# 02.net
KiCad netlist of a schematic drawn in Altium Designer
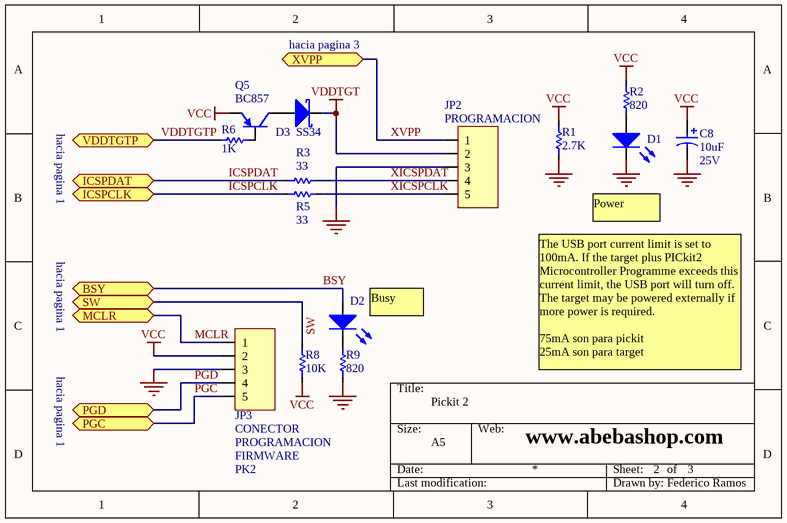
[diagram p0: 02.SchDoc]

(export (version "E")
  (design (tool "Eeschema 10.0.6"))
  (components
    (comp (ref "C8")
      (value "10uF")
      (footprint "1206P")
      (description "Capacitor Polarizado")
      (fields (field (name "VOLTAJE") "25V") (field (name "Comment") "Cap Pol"))
      (libsource (lib "FEDE") (part "Cap Pol"))
    )
    (comp (ref "D1")
      (value "LED")
      (footprint "1206P")
      (description "Led")
      (libsource (lib "FEDE") (part "LED"))
    )
    (comp (ref "D2")
      (value "LED")
      (footprint "1206P")
      (description "Led")
      (libsource (lib "FEDE") (part "LED"))
    )
    (comp (ref "D3")
      (value "SS34")
      (footprint "D64")
      (description "Schottky Diode 3A 40V")
      (libsource (lib "FEDE") (part "1N5822"))
    )
    (comp (ref "JP2")
      (value "Header5x1")
      (footprint "HDR5x1")
      (description "Header 5x1")
      (fields (field (name "PRICE") "PROGRAMACION"))
      (libsource (lib "FEDE") (part "Header5x1"))
    )
    (comp (ref "JP3")
      (value "Header5x1")
      (footprint "HDR5x1")
      (description "Header 5x1")
      (fields
        (field (name "PRICE") "CONECTOR")
        (field (name "ALTIUM_UNNAMED_1") "PROGRAMACION")
        (field (name "ALTIUM_UNNAMED_2") "FIRMWARE")
        (field (name "ALTIUM_UNNAMED_3") "PK2")
      )
      (libsource (lib "FEDE") (part "Header5x1"))
    )
    (comp (ref "Q5")
      (value "BC857")
      (footprint "SOT23")
      (description "100mA 65V PNP Bipolar Transistor")
      (libsource (lib "FEDE") (part "BC856A"))
    )
    (comp (ref "R1")
      (value "2.7K")
      (footprint "1206NP")
      (description "Resistor")
      (fields (field (name "POWER") "0.25W") (field (name "Comment") "Res"))
      (libsource (lib "FEDE") (part "Res"))
    )
    (comp (ref "R2")
      (value "820")
      (footprint "1206NP")
      (description "Resistor")
      (fields (field (name "POWER") "0.25W") (field (name "Comment") "Res"))
      (libsource (lib "FEDE") (part "Res"))
    )
    (comp (ref "R3")
      (value "33")
      (footprint "1206NP")
      (description "Resistor")
      (fields (field (name "POWER") "0.25W") (field (name "Comment") "Res"))
      (libsource (lib "FEDE") (part "Res"))
    )
    (comp (ref "R5")
      (value "33")
      (footprint "1206NP")
      (description "Resistor")
      (fields (field (name "POWER") "0.25W") (field (name "Comment") "Res"))
      (libsource (lib "FEDE") (part "Res"))
    )
    (comp (ref "R6")
      (value "1K")
      (footprint "1206NP")
      (description "Resistor")
      (fields (field (name "POWER") "0.25W") (field (name "Comment") "Res"))
      (libsource (lib "FEDE") (part "Res"))
    )
    (comp (ref "R8")
      (value "10K")
      (footprint "1206NP")
      (description "Resistor")
      (fields (field (name "POWER") "0.25W") (field (name "Comment") "Res"))
      (libsource (lib "FEDE") (part "Res"))
    )
    (comp (ref "R9")
      (value "820")
      (footprint "1206NP")
      (description "Resistor")
      (fields (field (name "POWER") "0.25W") (field (name "Comment") "Res"))
      (libsource (lib "FEDE") (part "Res"))
    )
  )
  (nets
    (net (code "1") (name "/BSY") (class "Default")
      (node (ref "D2") (pin "1") (pinfunction "A_1") (pintype "passive"))
    )
    (net (code "2") (name "/ICSPCLK") (class "Default")
      (node (ref "R5") (pin "1") (pinfunction "1_1") (pintype "passive"))
    )
    (net (code "3") (name "/ICSPDAT") (class "Default")
      (node (ref "R3") (pin "1") (pinfunction "1_1") (pintype "passive"))
    )
    (net (code "4") (name "/MCLR") (class "Default")
      (node (ref "JP3") (pin "1") (pinfunction "1_1") (pintype "passive"))
    )
    (net (code "5") (name "/PGC") (class "Default")
      (node (ref "JP3") (pin "5") (pinfunction "5_5") (pintype "passive"))
    )
    (net (code "6") (name "/PGD") (class "Default")
      (node (ref "JP3") (pin "4") (pinfunction "4_4") (pintype "passive"))
    )
    (net (code "7") (name "/SW") (class "Default")
      (node (ref "R8") (pin "1") (pinfunction "1_1") (pintype "passive"))
    )
    (net (code "8") (name "/VDDTGTP") (class "Default")
      (node (ref "R6") (pin "2") (pinfunction "2_2") (pintype "passive"))
    )
    (net (code "9") (name "/XICSPCLK") (class "Default")
      (node (ref "JP2") (pin "5") (pinfunction "5_5") (pintype "passive"))
      (node (ref "R5") (pin "2") (pinfunction "2_2") (pintype "passive"))
    )
    (net (code "10") (name "/XICSPDAT") (class "Default")
      (node (ref "JP2") (pin "4") (pinfunction "4_4") (pintype "passive"))
      (node (ref "R3") (pin "2") (pinfunction "2_2") (pintype "passive"))
    )
    (net (code "11") (name "/XVPP") (class "Default")
      (node (ref "JP2") (pin "1") (pinfunction "1_1") (pintype "passive"))
    )
    (net (code "12") (name "GND") (class "Default")
      (node (ref "C8") (pin "2") (pinfunction "2_2") (pintype "passive"))
      (node (ref "D1") (pin "2") (pinfunction "K_2") (pintype "passive"))
      (node (ref "JP2") (pin "3") (pinfunction "3_3") (pintype "passive"))
      (node (ref "JP3") (pin "3") (pinfunction "3_3") (pintype "passive"))
      (node (ref "R1") (pin "2") (pinfunction "2_2") (pintype "passive"))
      (node (ref "R9") (pin "1") (pinfunction "1_1") (pintype "passive"))
    )
    (net (code "13") (name "Net-(D1-A)") (class "Default")
      (node (ref "D1") (pin "1") (pinfunction "A_1") (pintype "passive"))
      (node (ref "R2") (pin "1") (pinfunction "1_1") (pintype "passive"))
    )
    (net (code "14") (name "Net-(D2-K)") (class "Default")
      (node (ref "D2") (pin "2") (pinfunction "K_2") (pintype "passive"))
      (node (ref "R9") (pin "2") (pinfunction "2_2") (pintype "passive"))
    )
    (net (code "15") (name "Net-(D3-A)") (class "Default")
      (node (ref "D3") (pin "1") (pinfunction "A_1") (pintype "passive"))
      (node (ref "Q5") (pin "1") (pinfunction "C_1") (pintype "passive"))
    )
    (net (code "16") (name "Net-(Q5-B)") (class "Default")
      (node (ref "Q5") (pin "2") (pinfunction "B_2") (pintype "passive"))
      (node (ref "R6") (pin "1") (pinfunction "1_1") (pintype "passive"))
    )
    (net (code "17") (name "VCC") (class "Default")
      (node (ref "C8") (pin "1") (pinfunction "1_1") (pintype "passive"))
      (node (ref "JP3") (pin "2") (pinfunction "2_2") (pintype "passive"))
      (node (ref "Q5") (pin "3") (pinfunction "E_3") (pintype "passive"))
      (node (ref "R1") (pin "1") (pinfunction "1_1") (pintype "passive"))
      (node (ref "R2") (pin "2") (pinfunction "2_2") (pintype "passive"))
      (node (ref "R8") (pin "2") (pinfunction "2_2") (pintype "passive"))
    )
    (net (code "18") (name "VDDTGT") (class "Default")
      (node (ref "D3") (pin "2") (pinfunction "K_2") (pintype "passive"))
      (node (ref "JP2") (pin "2") (pinfunction "2_2") (pintype "passive"))
    )
  )
)
